# Mega_Amp_2_6.net
KiCad netlist of a schematic drawn in EAGLE
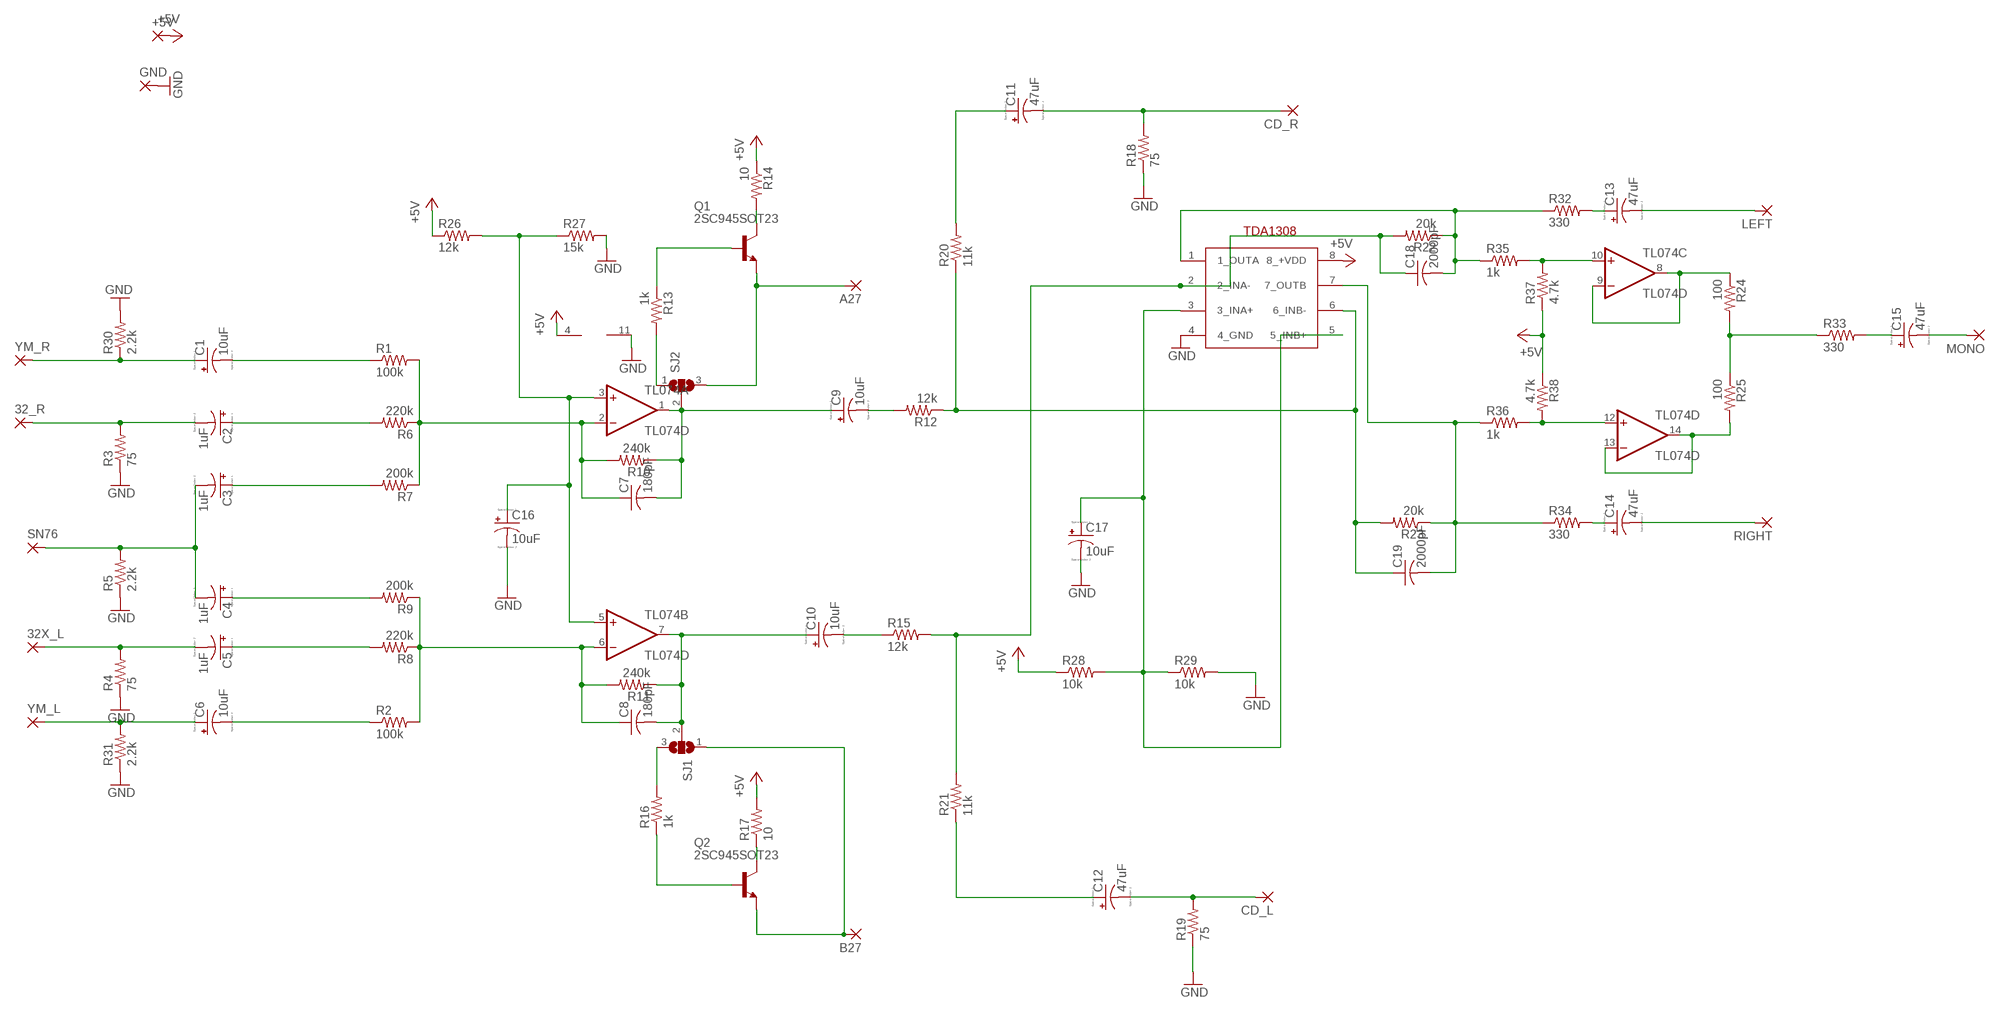
[diagram p0: schematic, sheet 1]

(export (version "E")
  (design (tool "Eeschema 10.0.6"))
  (components
    (comp (ref "+5V")
      (value "SMD5")
      (footprint "eagle-import:SMD2,54-5,08")
      (libsource (lib "eagle-import") (part "SMD5"))
    )
    (comp (ref "32X_L")
      (value "SMD2")
      (footprint "eagle-import:SMD1,27-2,54")
      (libsource (lib "eagle-import") (part "SMD2"))
    )
    (comp (ref "32_R")
      (value "SMD2")
      (footprint "eagle-import:SMD1,27-2,54")
      (libsource (lib "eagle-import") (part "SMD2"))
    )
    (comp (ref "A27")
      (value "SMD2")
      (footprint "eagle-import:SMD1,27-2,54")
      (libsource (lib "eagle-import") (part "SMD2"))
    )
    (comp (ref "B27")
      (value "SMD2")
      (footprint "eagle-import:SMD1,27-2,54")
      (libsource (lib "eagle-import") (part "SMD2"))
    )
    (comp (ref "C1")
      (value "10uF")
      (footprint "eagle-import:153CLV-0405")
      (libsource (lib "eagle-import") (part "CPOL-US153CLV-0405"))
    )
    (comp (ref "C2")
      (value "1uF")
      (footprint "eagle-import:153CLV-0405")
      (libsource (lib "eagle-import") (part "CPOL-US153CLV-0405"))
    )
    (comp (ref "C3")
      (value "1uF")
      (footprint "eagle-import:153CLV-0405")
      (libsource (lib "eagle-import") (part "CPOL-US153CLV-0405"))
    )
    (comp (ref "C4")
      (value "1uF")
      (footprint "eagle-import:153CLV-0405")
      (libsource (lib "eagle-import") (part "CPOL-US153CLV-0405"))
    )
    (comp (ref "C5")
      (value "1uF")
      (footprint "eagle-import:153CLV-0405")
      (libsource (lib "eagle-import") (part "CPOL-US153CLV-0405"))
    )
    (comp (ref "C6")
      (value "10uF")
      (footprint "eagle-import:153CLV-0405")
      (libsource (lib "eagle-import") (part "CPOL-US153CLV-0405"))
    )
    (comp (ref "C7")
      (value "180pF")
      (footprint "eagle-import:C0603")
      (libsource (lib "eagle-import") (part "resistor_348_C-USC0603"))
    )
    (comp (ref "C8")
      (value "180pF")
      (footprint "eagle-import:C0603")
      (libsource (lib "eagle-import") (part "C-USC0603"))
    )
    (comp (ref "C9")
      (value "10uF")
      (footprint "eagle-import:153CLV-0405")
      (libsource (lib "eagle-import") (part "CPOL-US153CLV-0405"))
    )
    (comp (ref "C10")
      (value "10uF")
      (footprint "eagle-import:153CLV-0405")
      (libsource (lib "eagle-import") (part "CPOL-US153CLV-0405"))
    )
    (comp (ref "C11")
      (value "47uF")
      (footprint "eagle-import:153CLV-0505")
      (libsource (lib "eagle-import") (part "CPOL-US153CLV-0505"))
    )
    (comp (ref "C12")
      (value "47uF")
      (footprint "eagle-import:153CLV-0505")
      (libsource (lib "eagle-import") (part "CPOL-US153CLV-0505"))
    )
    (comp (ref "C13")
      (value "47uF")
      (footprint "eagle-import:153CLV-0505")
      (libsource (lib "eagle-import") (part "CPOL-US153CLV-0505"))
    )
    (comp (ref "C14")
      (value "47uF")
      (footprint "eagle-import:153CLV-0505")
      (libsource (lib "eagle-import") (part "CPOL-US153CLV-0505"))
    )
    (comp (ref "C15")
      (value "47uF")
      (footprint "eagle-import:153CLV-0505")
      (libsource (lib "eagle-import") (part "CPOL-US153CLV-0505"))
    )
    (comp (ref "C16")
      (value "10uF")
      (footprint "eagle-import:153CLV-0405")
      (libsource (lib "eagle-import") (part "CPOL-US153CLV-0405"))
    )
    (comp (ref "C17")
      (value "10uF")
      (footprint "eagle-import:153CLV-0405")
      (libsource (lib "eagle-import") (part "CPOL-US153CLV-0405"))
    )
    (comp (ref "C18")
      (value "2000pF")
      (footprint "eagle-import:C0603")
      (libsource (lib "eagle-import") (part "C-USC0603"))
    )
    (comp (ref "C19")
      (value "2000pF")
      (footprint "eagle-import:C0603")
      (libsource (lib "eagle-import") (part "C-USC0603"))
    )
    (comp (ref "CD_L")
      (value "SMD2")
      (footprint "eagle-import:SMD1,27-2,54")
      (libsource (lib "eagle-import") (part "SMD2"))
    )
    (comp (ref "CD_R")
      (value "SMD2")
      (footprint "eagle-import:SMD1,27-2,54")
      (libsource (lib "eagle-import") (part "SMD2"))
    )
    (comp (ref "GND")
      (value "SMD5")
      (footprint "eagle-import:SMD2,54-5,08")
      (libsource (lib "eagle-import") (part "SMD5"))
    )
    (comp (ref "LEFT")
      (value "SMD2")
      (footprint "eagle-import:SMD1,27-2,54")
      (libsource (lib "eagle-import") (part "SMD2"))
    )
    (comp (ref "MONO")
      (value "SMD2")
      (footprint "eagle-import:SMD1,27-2,54")
      (libsource (lib "eagle-import") (part "SMD2"))
    )
    (comp (ref "Q1")
      (value "2SC945SOT23")
      (footprint "eagle-import:SOT23")
      (libsource (lib "eagle-import") (part "2SC945SOT23"))
    )
    (comp (ref "Q2")
      (value "2SC945SOT23")
      (footprint "eagle-import:SOT23")
      (libsource (lib "eagle-import") (part "2SC945SOT23"))
    )
    (comp (ref "R1")
      (value "100k")
      (footprint "eagle-import:R0603")
      (libsource (lib "eagle-import") (part "R-US_R0603"))
    )
    (comp (ref "R2")
      (value "100k")
      (footprint "eagle-import:R0603")
      (libsource (lib "eagle-import") (part "R-US_R0603"))
    )
    (comp (ref "R3")
      (value "75")
      (footprint "eagle-import:R0603")
      (libsource (lib "eagle-import") (part "R-US_R0603"))
    )
    (comp (ref "R4")
      (value "75")
      (footprint "eagle-import:R0603")
      (libsource (lib "eagle-import") (part "R-US_R0603"))
    )
    (comp (ref "R5")
      (value "2.2k")
      (footprint "eagle-import:R0603")
      (libsource (lib "eagle-import") (part "R-US_R0603"))
    )
    (comp (ref "R6")
      (value "220k")
      (footprint "eagle-import:R0603")
      (libsource (lib "eagle-import") (part "R-US_R0603"))
    )
    (comp (ref "R7")
      (value "200k")
      (footprint "eagle-import:R0603")
      (libsource (lib "eagle-import") (part "R-US_R0603"))
    )
    (comp (ref "R8")
      (value "220k")
      (footprint "eagle-import:R0603")
      (libsource (lib "eagle-import") (part "R-US_R0603"))
    )
    (comp (ref "R9")
      (value "200k")
      (footprint "eagle-import:R0603")
      (libsource (lib "eagle-import") (part "R-US_R0603"))
    )
    (comp (ref "R10")
      (value "240k")
      (footprint "eagle-import:R0603")
      (libsource (lib "eagle-import") (part "R-US_R0603"))
    )
    (comp (ref "R11")
      (value "240k")
      (footprint "eagle-import:R0603")
      (libsource (lib "eagle-import") (part "R-US_R0603"))
    )
    (comp (ref "R12")
      (value "12k")
      (footprint "eagle-import:R0603")
      (libsource (lib "eagle-import") (part "R-US_R0603"))
    )
    (comp (ref "R13")
      (value "1k")
      (footprint "eagle-import:R0603")
      (libsource (lib "eagle-import") (part "R-US_R0603"))
    )
    (comp (ref "R14")
      (value "10")
      (footprint "eagle-import:R0603")
      (libsource (lib "eagle-import") (part "R-US_R0603"))
    )
    (comp (ref "R15")
      (value "12k")
      (footprint "eagle-import:R0603")
      (libsource (lib "eagle-import") (part "R-US_R0603"))
    )
    (comp (ref "R16")
      (value "1k")
      (footprint "eagle-import:R0603")
      (libsource (lib "eagle-import") (part "R-US_R0603"))
    )
    (comp (ref "R17")
      (value "10")
      (footprint "eagle-import:R0603")
      (libsource (lib "eagle-import") (part "R-US_R0603"))
    )
    (comp (ref "R18")
      (value "75")
      (footprint "eagle-import:R0603")
      (libsource (lib "eagle-import") (part "R-US_R0603"))
    )
    (comp (ref "R19")
      (value "75")
      (footprint "eagle-import:R0603")
      (libsource (lib "eagle-import") (part "R-US_R0603"))
    )
    (comp (ref "R20")
      (value "11k")
      (footprint "eagle-import:R0603")
      (libsource (lib "eagle-import") (part "R-US_R0603"))
    )
    (comp (ref "R21")
      (value "11k")
      (footprint "eagle-import:R0603")
      (libsource (lib "eagle-import") (part "R-US_R0603"))
    )
    (comp (ref "R22")
      (value "20k")
      (footprint "eagle-import:R0603")
      (libsource (lib "eagle-import") (part "R-US_R0603"))
    )
    (comp (ref "R23")
      (value "20k")
      (footprint "eagle-import:R0603")
      (libsource (lib "eagle-import") (part "R-US_R0603"))
    )
    (comp (ref "R24")
      (value "100")
      (footprint "eagle-import:R0603")
      (libsource (lib "eagle-import") (part "R-US_R0603"))
    )
    (comp (ref "R25")
      (value "100")
      (footprint "eagle-import:R0603")
      (libsource (lib "eagle-import") (part "R-US_R0603"))
    )
    (comp (ref "R26")
      (value "12k")
      (footprint "eagle-import:R0603")
      (libsource (lib "eagle-import") (part "R-US_R0603"))
    )
    (comp (ref "R27")
      (value "15k")
      (footprint "eagle-import:R0603")
      (libsource (lib "eagle-import") (part "R-US_R0603"))
    )
    (comp (ref "R28")
      (value "10k")
      (footprint "eagle-import:R0603")
      (libsource (lib "eagle-import") (part "R-US_R0603"))
    )
    (comp (ref "R29")
      (value "10k")
      (footprint "eagle-import:R0603")
      (libsource (lib "eagle-import") (part "R-US_R0603"))
    )
    (comp (ref "R30")
      (value "2.2k")
      (footprint "eagle-import:R0603")
      (libsource (lib "eagle-import") (part "resistor_348_R-US_R0603"))
    )
    (comp (ref "R31")
      (value "2.2k")
      (footprint "eagle-import:R0603")
      (libsource (lib "eagle-import") (part "R-US_R0603"))
    )
    (comp (ref "R32")
      (value "330")
      (footprint "eagle-import:R0603")
      (libsource (lib "eagle-import") (part "resistor_348_R-US_R0603"))
    )
    (comp (ref "R33")
      (value "330")
      (footprint "eagle-import:R0603")
      (libsource (lib "eagle-import") (part "resistor_348_R-US_R0603"))
    )
    (comp (ref "R34")
      (value "330")
      (footprint "eagle-import:R0603")
      (libsource (lib "eagle-import") (part "resistor_348_R-US_R0603"))
    )
    (comp (ref "R35")
      (value "1k")
      (footprint "eagle-import:R0603")
      (libsource (lib "eagle-import") (part "R-US_R0603"))
    )
    (comp (ref "R36")
      (value "1k")
      (footprint "eagle-import:R0603")
      (libsource (lib "eagle-import") (part "R-US_R0603"))
    )
    (comp (ref "R37")
      (value "4.7k")
      (footprint "eagle-import:R0603")
      (libsource (lib "eagle-import") (part "R-US_R0603"))
    )
    (comp (ref "R38")
      (value "4.7k")
      (footprint "eagle-import:R0603")
      (libsource (lib "eagle-import") (part "R-US_R0603"))
    )
    (comp (ref "RIGHT")
      (value "SMD2")
      (footprint "eagle-import:SMD1,27-2,54")
      (libsource (lib "eagle-import") (part "SMD2"))
    )
    (comp (ref "SJ1")
      (value "SJ2W")
      (footprint "eagle-import:SJ_2")
      (libsource (lib "eagle-import") (part "SJ2W"))
    )
    (comp (ref "SJ2")
      (value "SJ2W")
      (footprint "eagle-import:SJ_2")
      (libsource (lib "eagle-import") (part "SJ2W"))
    )
    (comp (ref "SN76")
      (value "SMD2")
      (footprint "eagle-import:SMD1,27-2,54")
      (libsource (lib "eagle-import") (part "SMD2"))
    )
    (comp (ref "TDA1308")
      (value "TDA1308SO8")
      (footprint "eagle-import:SO8")
      (libsource (lib "eagle-import") (part "TDA1308SO8"))
    )
    (comp (ref "TL074")
      (value "TL074D")
      (footprint "eagle-import:SO14")
      (libsource (lib "eagle-import") (part "TL074D"))
    )
    (comp (ref "YM_L")
      (value "SMD2")
      (footprint "eagle-import:SMD1,27-2,54")
      (libsource (lib "eagle-import") (part "SMD2"))
    )
    (comp (ref "YM_R")
      (value "SMD2")
      (footprint "eagle-import:SMD1,27-2,54")
      (libsource (lib "eagle-import") (part "SMD2"))
    )
  )
  (nets
    (net (code "1") (name "+5V") (class "Default")
      (node (ref "+5V") (pin "1") (pinfunction "P_1") (pintype "passive"))
      (node (ref "R14") (pin "1") (pinfunction "1_1") (pintype "passive"))
      (node (ref "R17") (pin "2") (pinfunction "2_2") (pintype "passive"))
      (node (ref "R26") (pin "1") (pinfunction "1_1") (pintype "passive"))
      (node (ref "R28") (pin "1") (pinfunction "1_1") (pintype "passive"))
      (node (ref "R37") (pin "1") (pinfunction "1_1") (pintype "passive"))
      (node (ref "R38") (pin "1") (pinfunction "1_1") (pintype "passive"))
      (node (ref "TDA1308") (pin "8") (pinfunction "8_+VDD_8") (pintype "bidirectional"))
      (node (ref "TL074") (pin "4") (pinfunction "V+_4") (pintype "power_in"))
    )
    (net (code "2") (name "GND") (class "Default")
      (node (ref "C16") (pin "-") (pinfunction "-_-") (pintype "passive"))
      (node (ref "C17") (pin "-") (pinfunction "-_-") (pintype "passive"))
      (node (ref "GND") (pin "1") (pinfunction "P_1") (pintype "passive"))
      (node (ref "R18") (pin "1") (pinfunction "1_1") (pintype "passive"))
      (node (ref "R19") (pin "1") (pinfunction "1_1") (pintype "passive"))
      (node (ref "R27") (pin "2") (pinfunction "2_2") (pintype "passive"))
      (node (ref "R29") (pin "2") (pinfunction "2_2") (pintype "passive"))
      (node (ref "R3") (pin "1") (pinfunction "1_1") (pintype "passive"))
      (node (ref "R30") (pin "2") (pinfunction "2_2") (pintype "passive"))
      (node (ref "R31") (pin "1") (pinfunction "1_1") (pintype "passive"))
      (node (ref "R4") (pin "1") (pinfunction "1_1") (pintype "passive"))
      (node (ref "R5") (pin "1") (pinfunction "1_1") (pintype "passive"))
      (node (ref "TDA1308") (pin "4") (pinfunction "4_GND_4") (pintype "bidirectional"))
      (node (ref "TL074") (pin "11") (pinfunction "V-_11") (pintype "power_in"))
    )
    (net (code "3") (name "Net-(32X_L-P)") (class "Default")
      (node (ref "32X_L") (pin "1") (pinfunction "P_1") (pintype "passive"))
      (node (ref "C5") (pin "-") (pinfunction "-_-") (pintype "passive"))
      (node (ref "R4") (pin "2") (pinfunction "2_2") (pintype "passive"))
    )
    (net (code "4") (name "Net-(32_R-P)") (class "Default")
      (node (ref "32_R") (pin "1") (pinfunction "P_1") (pintype "passive"))
      (node (ref "C2") (pin "-") (pinfunction "-_-") (pintype "passive"))
      (node (ref "R3") (pin "2") (pinfunction "2_2") (pintype "passive"))
    )
    (net (code "5") (name "Net-(A27-P)") (class "Default")
      (node (ref "A27") (pin "1") (pinfunction "P_1") (pintype "passive"))
      (node (ref "Q1") (pin "2") (pinfunction "E_2") (pintype "passive"))
      (node (ref "SJ2") (pin "3") (pinfunction "3_3") (pintype "passive"))
    )
    (net (code "6") (name "Net-(B27-P)") (class "Default")
      (node (ref "B27") (pin "1") (pinfunction "P_1") (pintype "passive"))
      (node (ref "Q2") (pin "2") (pinfunction "E_2") (pintype "passive"))
      (node (ref "SJ1") (pin "1") (pinfunction "1_1") (pintype "passive"))
    )
    (net (code "7") (name "Net-(C1-Pad-)") (class "Default")
      (node (ref "C1") (pin "-") (pinfunction "-_-") (pintype "passive"))
      (node (ref "R1") (pin "1") (pinfunction "1_1") (pintype "passive"))
    )
    (net (code "8") (name "Net-(C2-Pad+)") (class "Default")
      (node (ref "C2") (pin "+") (pinfunction "+_+") (pintype "passive"))
      (node (ref "R6") (pin "2") (pinfunction "2_2") (pintype "passive"))
    )
    (net (code "9") (name "Net-(C3-Pad+)") (class "Default")
      (node (ref "C3") (pin "+") (pinfunction "+_+") (pintype "passive"))
      (node (ref "R7") (pin "2") (pinfunction "2_2") (pintype "passive"))
    )
    (net (code "10") (name "Net-(C4-Pad+)") (class "Default")
      (node (ref "C4") (pin "+") (pinfunction "+_+") (pintype "passive"))
      (node (ref "R9") (pin "2") (pinfunction "2_2") (pintype "passive"))
    )
    (net (code "11") (name "Net-(C5-Pad+)") (class "Default")
      (node (ref "C5") (pin "+") (pinfunction "+_+") (pintype "passive"))
      (node (ref "R8") (pin "2") (pinfunction "2_2") (pintype "passive"))
    )
    (net (code "12") (name "Net-(C6-Pad-)") (class "Default")
      (node (ref "C6") (pin "-") (pinfunction "-_-") (pintype "passive"))
      (node (ref "R2") (pin "1") (pinfunction "1_1") (pintype "passive"))
    )
    (net (code "13") (name "Net-(C9-Pad-)") (class "Default")
      (node (ref "C9") (pin "-") (pinfunction "-_-") (pintype "passive"))
      (node (ref "R12") (pin "2") (pinfunction "2_2") (pintype "passive"))
    )
    (net (code "14") (name "Net-(C10-Pad-)") (class "Default")
      (node (ref "C10") (pin "-") (pinfunction "-_-") (pintype "passive"))
      (node (ref "R15") (pin "1") (pinfunction "1_1") (pintype "passive"))
    )
    (net (code "15") (name "Net-(C11-Pad+)") (class "Default")
      (node (ref "C11") (pin "+") (pinfunction "+_+") (pintype "passive"))
      (node (ref "R20") (pin "2") (pinfunction "2_2") (pintype "passive"))
    )
    (net (code "16") (name "Net-(C12-Pad+)") (class "Default")
      (node (ref "C12") (pin "+") (pinfunction "+_+") (pintype "passive"))
      (node (ref "R21") (pin "1") (pinfunction "1_1") (pintype "passive"))
    )
    (net (code "17") (name "Net-(C13-Pad+)") (class "Default")
      (node (ref "C13") (pin "+") (pinfunction "+_+") (pintype "passive"))
      (node (ref "R32") (pin "2") (pinfunction "2_2") (pintype "passive"))
    )
    (net (code "18") (name "Net-(C14-Pad+)") (class "Default")
      (node (ref "C14") (pin "+") (pinfunction "+_+") (pintype "passive"))
      (node (ref "R34") (pin "2") (pinfunction "2_2") (pintype "passive"))
    )
    (net (code "19") (name "Net-(C15-Pad+)") (class "Default")
      (node (ref "C15") (pin "+") (pinfunction "+_+") (pintype "passive"))
      (node (ref "R33") (pin "2") (pinfunction "2_2") (pintype "passive"))
    )
    (net (code "20") (name "Net-(CD_L-P)") (class "Default")
      (node (ref "C12") (pin "-") (pinfunction "-_-") (pintype "passive"))
      (node (ref "CD_L") (pin "1") (pinfunction "P_1") (pintype "passive"))
      (node (ref "R19") (pin "2") (pinfunction "2_2") (pintype "passive"))
    )
    (net (code "21") (name "Net-(CD_R-P)") (class "Default")
      (node (ref "C11") (pin "-") (pinfunction "-_-") (pintype "passive"))
      (node (ref "CD_R") (pin "1") (pinfunction "P_1") (pintype "passive"))
      (node (ref "R18") (pin "2") (pinfunction "2_2") (pintype "passive"))
    )
    (net (code "22") (name "Net-(LEFT-P)") (class "Default")
      (node (ref "C13") (pin "-") (pinfunction "-_-") (pintype "passive"))
      (node (ref "LEFT") (pin "1") (pinfunction "P_1") (pintype "passive"))
    )
    (net (code "23") (name "Net-(MONO-P)") (class "Default")
      (node (ref "C15") (pin "-") (pinfunction "-_-") (pintype "passive"))
      (node (ref "MONO") (pin "1") (pinfunction "P_1") (pintype "passive"))
    )
    (net (code "24") (name "Net-(Q1-B)") (class "Default")
      (node (ref "Q1") (pin "1") (pinfunction "B_1") (pintype "passive"))
      (node (ref "R13") (pin "1") (pinfunction "1_1") (pintype "passive"))
    )
    (net (code "25") (name "Net-(Q1-C)") (class "Default")
      (node (ref "Q1") (pin "3") (pinfunction "C_3") (pintype "passive"))
      (node (ref "R14") (pin "2") (pinfunction "2_2") (pintype "passive"))
    )
    (net (code "26") (name "Net-(Q2-B)") (class "Default")
      (node (ref "Q2") (pin "1") (pinfunction "B_1") (pintype "passive"))
      (node (ref "R16") (pin "1") (pinfunction "1_1") (pintype "passive"))
    )
    (net (code "27") (name "Net-(Q2-C)") (class "Default")
      (node (ref "Q2") (pin "3") (pinfunction "C_3") (pintype "passive"))
      (node (ref "R17") (pin "1") (pinfunction "1_1") (pintype "passive"))
    )
    (net (code "28") (name "Net-(R13-Pad2)") (class "Default")
      (node (ref "R13") (pin "2") (pinfunction "2_2") (pintype "passive"))
      (node (ref "SJ2") (pin "1") (pinfunction "1_1") (pintype "passive"))
    )
    (net (code "29") (name "Net-(R16-Pad2)") (class "Default")
      (node (ref "R16") (pin "2") (pinfunction "2_2") (pintype "passive"))
      (node (ref "SJ1") (pin "3") (pinfunction "3_3") (pintype "passive"))
    )
    (net (code "30") (name "Net-(R24-Pad2)") (class "Default")
      (node (ref "R24") (pin "2") (pinfunction "2_2") (pintype "passive"))
      (node (ref "R25") (pin "1") (pinfunction "1_1") (pintype "passive"))
      (node (ref "R33") (pin "1") (pinfunction "1_1") (pintype "passive"))
    )
    (net (code "31") (name "Net-(RIGHT-P)") (class "Default")
      (node (ref "C14") (pin "-") (pinfunction "-_-") (pintype "passive"))
      (node (ref "RIGHT") (pin "1") (pinfunction "P_1") (pintype "passive"))
    )
    (net (code "32") (name "Net-(SN76-P)") (class "Default")
      (node (ref "C3") (pin "-") (pinfunction "-_-") (pintype "passive"))
      (node (ref "C4") (pin "-") (pinfunction "-_-") (pintype "passive"))
      (node (ref "R5") (pin "2") (pinfunction "2_2") (pintype "passive"))
      (node (ref "SN76") (pin "1") (pinfunction "P_1") (pintype "passive"))
    )
    (net (code "33") (name "Net-(TDA1308-1_OUTA)") (class "Default")
      (node (ref "C18") (pin "2") (pinfunction "2_2") (pintype "passive"))
      (node (ref "R22") (pin "1") (pinfunction "1_1") (pintype "passive"))
      (node (ref "R32") (pin "1") (pinfunction "1_1") (pintype "passive"))
      (node (ref "R35") (pin "1") (pinfunction "1_1") (pintype "passive"))
      (node (ref "TDA1308") (pin "1") (pinfunction "1_OUTA_1") (pintype "bidirectional"))
    )
    (net (code "34") (name "Net-(TDA1308-2_INA-)") (class "Default")
      (node (ref "C18") (pin "1") (pinfunction "1_1") (pintype "passive"))
      (node (ref "R15") (pin "2") (pinfunction "2_2") (pintype "passive"))
      (node (ref "R21") (pin "2") (pinfunction "2_2") (pintype "passive"))
      (node (ref "R22") (pin "2") (pinfunction "2_2") (pintype "passive"))
      (node (ref "TDA1308") (pin "2") (pinfunction "2_INA-_2") (pintype "bidirectional"))
    )
    (net (code "35") (name "Net-(TDA1308-3_INA+)") (class "Default")
      (node (ref "C17") (pin "+") (pinfunction "+_+") (pintype "passive"))
      (node (ref "R28") (pin "2") (pinfunction "2_2") (pintype "passive"))
      (node (ref "R29") (pin "1") (pinfunction "1_1") (pintype "passive"))
      (node (ref "TDA1308") (pin "3") (pinfunction "3_INA+_3") (pintype "bidirectional"))
      (node (ref "TDA1308") (pin "5") (pinfunction "5_INB+_5") (pintype "bidirectional"))
    )
    (net (code "36") (name "Net-(TDA1308-6_INB-)") (class "Default")
      (node (ref "C19") (pin "1") (pinfunction "1_1") (pintype "passive"))
      (node (ref "R12") (pin "1") (pinfunction "1_1") (pintype "passive"))
      (node (ref "R20") (pin "1") (pinfunction "1_1") (pintype "passive"))
      (node (ref "R23") (pin "2") (pinfunction "2_2") (pintype "passive"))
      (node (ref "TDA1308") (pin "6") (pinfunction "6_INB-_6") (pintype "bidirectional"))
    )
    (net (code "37") (name "Net-(TDA1308-7_OUTB)") (class "Default")
      (node (ref "C19") (pin "2") (pinfunction "2_2") (pintype "passive"))
      (node (ref "R23") (pin "1") (pinfunction "1_1") (pintype "passive"))
      (node (ref "R34") (pin "1") (pinfunction "1_1") (pintype "passive"))
      (node (ref "R36") (pin "1") (pinfunction "1_1") (pintype "passive"))
      (node (ref "TDA1308") (pin "7") (pinfunction "7_OUTB_7") (pintype "bidirectional"))
    )
    (net (code "38") (name "Net-(TL074A-+IN)") (class "Default")
      (node (ref "C16") (pin "+") (pinfunction "+_+") (pintype "passive"))
      (node (ref "R26") (pin "2") (pinfunction "2_2") (pintype "passive"))
      (node (ref "R27") (pin "1") (pinfunction "1_1") (pintype "passive"))
      (node (ref "TL074") (pin "3") (pinfunction "+IN_3") (pintype "input"))
      (node (ref "TL074") (pin "5") (pinfunction "+IN_5") (pintype "input"))
    )
    (net (code "39") (name "Net-(TL074A--IN)") (class "Default")
      (node (ref "C7") (pin "1") (pinfunction "1_1") (pintype "passive"))
      (node (ref "R1") (pin "2") (pinfunction "2_2") (pintype "passive"))
      (node (ref "R10") (pin "2") (pinfunction "2_2") (pintype "passive"))
      (node (ref "R6") (pin "1") (pinfunction "1_1") (pintype "passive"))
      (node (ref "R7") (pin "1") (pinfunction "1_1") (pintype "passive"))
      (node (ref "TL074") (pin "2") (pinfunction "-IN_2") (pintype "input"))
    )
    (net (code "40") (name "Net-(TL074A-OUT)") (class "Default")
      (node (ref "C7") (pin "2") (pinfunction "2_2") (pintype "passive"))
      (node (ref "C9") (pin "+") (pinfunction "+_+") (pintype "passive"))
      (node (ref "R10") (pin "1") (pinfunction "1_1") (pintype "passive"))
      (node (ref "SJ2") (pin "2") (pinfunction "2_2") (pintype "passive"))
      (node (ref "TL074") (pin "1") (pinfunction "OUT_1") (pintype "output"))
    )
    (net (code "41") (name "Net-(TL074B--IN)") (class "Default")
      (node (ref "C8") (pin "1") (pinfunction "1_1") (pintype "passive"))
      (node (ref "R11") (pin "2") (pinfunction "2_2") (pintype "passive"))
      (node (ref "R2") (pin "2") (pinfunction "2_2") (pintype "passive"))
      (node (ref "R8") (pin "1") (pinfunction "1_1") (pintype "passive"))
      (node (ref "R9") (pin "1") (pinfunction "1_1") (pintype "passive"))
      (node (ref "TL074") (pin "6") (pinfunction "-IN_6") (pintype "input"))
    )
    (net (code "42") (name "Net-(TL074B-OUT)") (class "Default")
      (node (ref "C10") (pin "+") (pinfunction "+_+") (pintype "passive"))
      (node (ref "C8") (pin "2") (pinfunction "2_2") (pintype "passive"))
      (node (ref "R11") (pin "1") (pinfunction "1_1") (pintype "passive"))
      (node (ref "SJ1") (pin "2") (pinfunction "2_2") (pintype "passive"))
      (node (ref "TL074") (pin "7") (pinfunction "OUT_7") (pintype "output"))
    )
    (net (code "43") (name "Net-(TL074C-+IN)") (class "Default")
      (node (ref "R35") (pin "2") (pinfunction "2_2") (pintype "passive"))
      (node (ref "R37") (pin "2") (pinfunction "2_2") (pintype "passive"))
      (node (ref "TL074") (pin "10") (pinfunction "+IN_10") (pintype "input"))
    )
    (net (code "44") (name "Net-(TL074C--IN)") (class "Default")
      (node (ref "R24") (pin "1") (pinfunction "1_1") (pintype "passive"))
      (node (ref "TL074") (pin "8") (pinfunction "OUT_8") (pintype "output"))
      (node (ref "TL074") (pin "9") (pinfunction "-IN_9") (pintype "input"))
    )
    (net (code "45") (name "Net-(TL074D-+IN)") (class "Default")
      (node (ref "R36") (pin "2") (pinfunction "2_2") (pintype "passive"))
      (node (ref "R38") (pin "2") (pinfunction "2_2") (pintype "passive"))
      (node (ref "TL074") (pin "12") (pinfunction "+IN_12") (pintype "input"))
    )
    (net (code "46") (name "Net-(TL074D--IN)") (class "Default")
      (node (ref "R25") (pin "2") (pinfunction "2_2") (pintype "passive"))
      (node (ref "TL074") (pin "13") (pinfunction "-IN_13") (pintype "input"))
      (node (ref "TL074") (pin "14") (pinfunction "OUT_14") (pintype "output"))
    )
    (net (code "47") (name "Net-(YM_L-P)") (class "Default")
      (node (ref "C6") (pin "+") (pinfunction "+_+") (pintype "passive"))
      (node (ref "R31") (pin "2") (pinfunction "2_2") (pintype "passive"))
      (node (ref "YM_L") (pin "1") (pinfunction "P_1") (pintype "passive"))
    )
    (net (code "48") (name "Net-(YM_R-P)") (class "Default")
      (node (ref "C1") (pin "+") (pinfunction "+_+") (pintype "passive"))
      (node (ref "R30") (pin "1") (pinfunction "1_1") (pintype "passive"))
      (node (ref "YM_R") (pin "1") (pinfunction "P_1") (pintype "passive"))
    )
  )
)
